# rz568m-power-data-v2.net
KiCad netlist of a schematic drawn in EAGLE
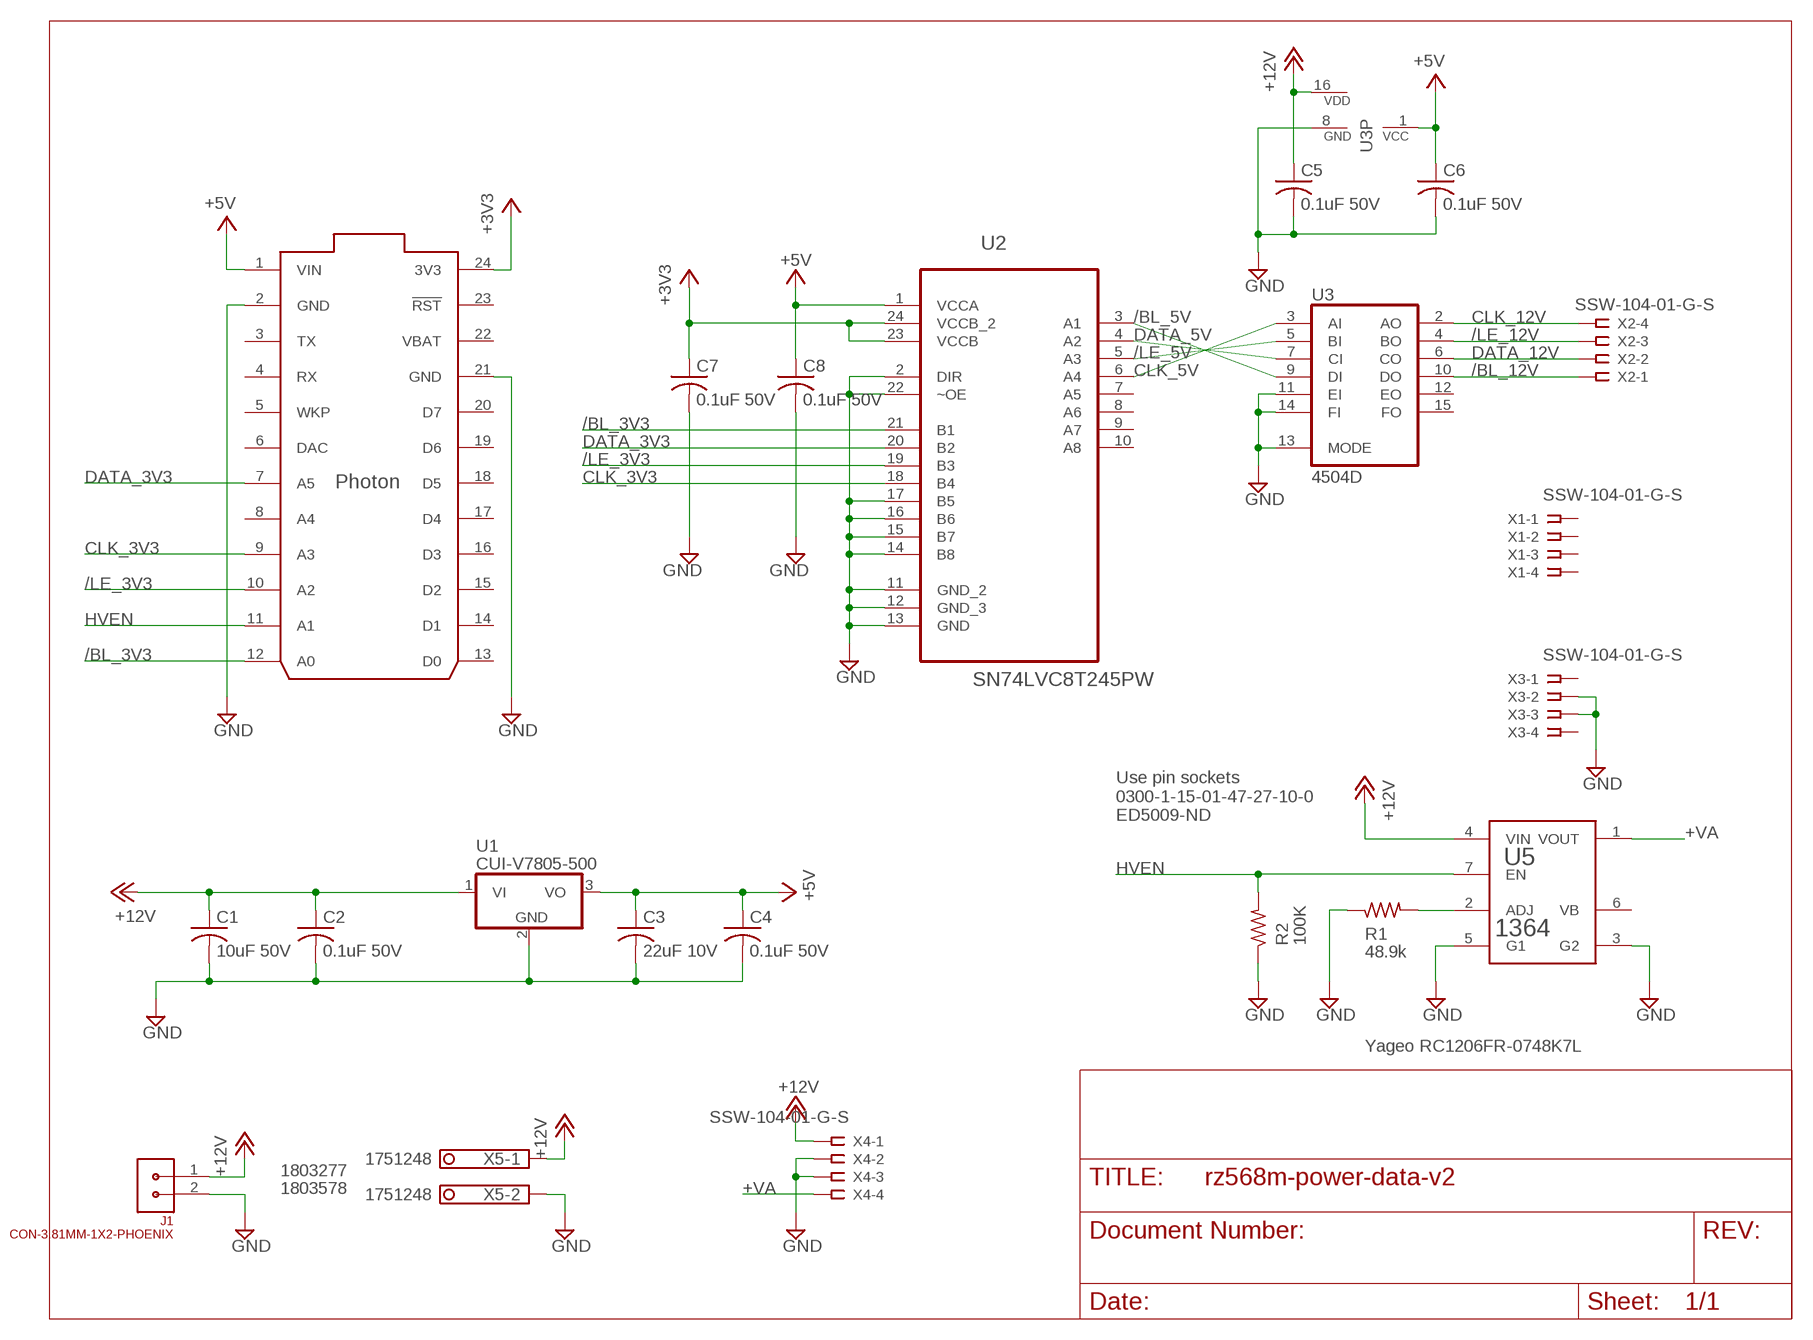
[diagram p0: schematic, sheet 1]

(export (version "E")
  (design (tool "Eeschema 10.0.6"))
  (components
    (comp (ref "C1")
      (value "10uF 50V")
      (footprint "eagle-import:C1210K")
      (fields (field (name "MFR") "KEMET") (field (name "MFR_PART_NO") "C1210C106K5RACTU"))
      (libsource (lib "eagle-import") (part "C-USC1210K"))
    )
    (comp (ref "C2")
      (value "0.1uF 50V")
      (footprint "eagle-import:C1206K")
      (fields (field (name "MFR") "KEMET") (field (name "MFR_PART_NO") "C1206S104M5RACTU"))
      (libsource (lib "eagle-import") (part "C-USC1206K"))
    )
    (comp (ref "C3")
      (value "22uF 10V")
      (footprint "eagle-import:C1206K")
      (fields (field (name "MFR") "KEMET") (field (name "MFR_PART_NO") "C1206C226K8RAC7800"))
      (libsource (lib "eagle-import") (part "C-USC1206K"))
    )
    (comp (ref "C4")
      (value "0.1uF 50V")
      (footprint "eagle-import:C1206K")
      (fields (field (name "MFR") "KEMET") (field (name "MFR_PART_NO") "C1206S104M5RACTU"))
      (libsource (lib "eagle-import") (part "C-USC1206K"))
    )
    (comp (ref "C5")
      (value "0.1uF 50V")
      (footprint "eagle-import:C0805K")
      (fields (field (name "MFR") "KEMET") (field (name "MFR_PART_NO") "C1206S104M5RACTU"))
      (libsource (lib "eagle-import") (part "C-USC0805K"))
    )
    (comp (ref "C6")
      (value "0.1uF 50V")
      (footprint "eagle-import:C0805K")
      (fields (field (name "MFR") "KEMET") (field (name "MFR_PART_NO") "C1206S104M5RACTU"))
      (libsource (lib "eagle-import") (part "C-USC0805K"))
    )
    (comp (ref "C7")
      (value "0.1uF 50V")
      (footprint "eagle-import:C0805K")
      (fields (field (name "MFR") "KEMET") (field (name "MFR_PART_NO") "C1206S104M5RACTU"))
      (libsource (lib "eagle-import") (part "C-USC0805K"))
    )
    (comp (ref "C8")
      (value "0.1uF 50V")
      (footprint "eagle-import:C0805K")
      (fields (field (name "MFR") "KEMET") (field (name "MFR_PART_NO") "C1206S104M5RACTU"))
      (libsource (lib "eagle-import") (part "C-USC0805K"))
    )
    (comp (ref "J1")
      (value "CON-3.81MM-1X2-PHOENIX")
      (footprint "eagle-import:CON-PHOENIX-3.81-1X2-RA")
      (libsource (lib "eagle-import") (part "CON-3.81MM-1X2-PHOENIX"))
    )
    (comp (ref "R1")
      (value "48.9k")
      (footprint "eagle-import:R1206")
      (libsource (lib "eagle-import") (part "R-US_R1206"))
    )
    (comp (ref "R2")
      (value "100K")
      (footprint "eagle-import:R1206")
      (libsource (lib "eagle-import") (part "R-US_R1206"))
    )
    (comp (ref "U1")
      (value "CUI-V7805-500")
      (footprint "eagle-import:CUI-78XX-500")
      (libsource (lib "eagle-import") (part "CUI-V7803-500"))
    )
    (comp (ref "U2")
      (value "SN74LVC8T245PW")
      (footprint "eagle-import:SOP65P640X120-24N")
      (fields (field (name "MPN") "SN74AVC8T245PW"))
      (libsource (lib "eagle-import") (part "SN74AVC8T245PW"))
    )
    (comp (ref "U3")
      (value "4504D")
      (footprint "eagle-import:SO16")
      (libsource (lib "eagle-import") (part "4504D"))
    )
    (comp (ref "U4")
      (value "PHOTON_WITH_HEADERS")
      (footprint "eagle-import:PHOTON")
      (libsource (lib "eagle-import") (part "PHOTON_WITH_HEADERS"))
    )
    (comp (ref "U5")
      (value "1364")
      (footprint "eagle-import:1364")
      (libsource (lib "eagle-import") (part "1364"))
    )
    (comp (ref "X1")
      (value "SSW-104-01-G-S")
      (footprint "eagle-import:SSW-104-02-S-S")
      (fields (field (name "MPN") "SSW-104-02-S-S"))
      (libsource (lib "eagle-import") (part "SSW-104-02-S-S"))
    )
    (comp (ref "X2")
      (value "SSW-104-01-G-S")
      (footprint "eagle-import:SSW-104-02-S-S")
      (fields (field (name "MPN") "SSW-104-02-S-S"))
      (libsource (lib "eagle-import") (part "SSW-104-02-S-S"))
    )
    (comp (ref "X3")
      (value "SSW-104-01-G-S")
      (footprint "eagle-import:SSW-104-02-S-S")
      (fields (field (name "MPN") "SSW-104-02-S-S"))
      (libsource (lib "eagle-import") (part "SSW-104-02-S-S"))
    )
    (comp (ref "X4")
      (value "SSW-104-01-G-S")
      (footprint "eagle-import:SSW-104-02-S-S")
      (fields (field (name "MPN") "SSW-104-02-S-S"))
      (libsource (lib "eagle-import") (part "SSW-104-02-S-S"))
    )
    (comp (ref "X5")
      (value "1751248")
      (footprint "eagle-import:1751248")
      (libsource (lib "eagle-import") (part "1751248"))
    )
  )
  (nets
    (net (code "1") (name "+3V3") (class "Default")
      (node (ref "C7") (pin "1") (pinfunction "1_1") (pintype "passive"))
      (node (ref "U2") (pin "23") (pinfunction "VCCB_23") (pintype "power_in"))
      (node (ref "U2") (pin "24") (pinfunction "VCCB_2_24") (pintype "power_in"))
      (node (ref "U4") (pin "24") (pinfunction "3V3_24") (pintype "power_in"))
    )
    (net (code "2") (name "+5V") (class "Default")
      (node (ref "C3") (pin "1") (pinfunction "1_1") (pintype "passive"))
      (node (ref "C4") (pin "1") (pinfunction "1_1") (pintype "passive"))
      (node (ref "C6") (pin "1") (pinfunction "1_1") (pintype "passive"))
      (node (ref "C8") (pin "1") (pinfunction "1_1") (pintype "passive"))
      (node (ref "U1") (pin "3") (pinfunction "VO_3") (pintype "passive"))
      (node (ref "U2") (pin "1") (pinfunction "VCCA_1") (pintype "power_in"))
      (node (ref "U3") (pin "1") (pinfunction "VCC_1") (pintype "power_in"))
      (node (ref "U4") (pin "1") (pinfunction "VIN_1") (pintype "power_in"))
    )
    (net (code "3") (name "+12V") (class "Default")
      (node (ref "C1") (pin "1") (pinfunction "1_1") (pintype "passive"))
      (node (ref "C2") (pin "1") (pinfunction "1_1") (pintype "passive"))
      (node (ref "C5") (pin "1") (pinfunction "1_1") (pintype "passive"))
      (node (ref "J1") (pin "1") (pinfunction "1_1") (pintype "bidirectional"))
      (node (ref "U1") (pin "1") (pinfunction "VI_1") (pintype "input"))
      (node (ref "U3") (pin "16") (pinfunction "VDD_16") (pintype "power_in"))
      (node (ref "U5") (pin "4") (pinfunction "VIN_4") (pintype "passive"))
      (node (ref "X4") (pin "1") (pinfunction "1_1") (pintype "passive"))
      (node (ref "X5") (pin "1") (pinfunction "K_1") (pintype "passive"))
    )
    (net (code "4") (name "/+VA") (class "Default")
      (node (ref "U5") (pin "1") (pinfunction "VOUT_1") (pintype "passive"))
      (node (ref "X4") (pin "4") (pinfunction "1_4") (pintype "passive"))
    )
    (net (code "5") (name "/CLK_3V3") (class "Default")
      (node (ref "U2") (pin "18") (pinfunction "B4_18") (pintype "bidirectional"))
      (node (ref "U4") (pin "9") (pinfunction "A3_9") (pintype "bidirectional"))
    )
    (net (code "6") (name "/CLK_5V") (class "Default")
      (node (ref "U2") (pin "6") (pinfunction "A4_6") (pintype "bidirectional"))
      (node (ref "U3") (pin "3") (pinfunction "AI_3") (pintype "input"))
    )
    (net (code "7") (name "/CLK_12V") (class "Default")
      (node (ref "U3") (pin "2") (pinfunction "AO_2") (pintype "output"))
      (node (ref "X2") (pin "4") (pinfunction "1_4") (pintype "passive"))
    )
    (net (code "8") (name "/DATA_3V3") (class "Default")
      (node (ref "U2") (pin "20") (pinfunction "B2_20") (pintype "bidirectional"))
      (node (ref "U4") (pin "7") (pinfunction "A5_7") (pintype "bidirectional"))
    )
    (net (code "9") (name "/DATA_5V") (class "Default")
      (node (ref "U2") (pin "4") (pinfunction "A2_4") (pintype "bidirectional"))
      (node (ref "U3") (pin "7") (pinfunction "CI_7") (pintype "input"))
    )
    (net (code "10") (name "/DATA_12V") (class "Default")
      (node (ref "U3") (pin "6") (pinfunction "CO_6") (pintype "output"))
      (node (ref "X2") (pin "2") (pinfunction "1_2") (pintype "passive"))
    )
    (net (code "11") (name "/HVEN") (class "Default")
      (node (ref "R2") (pin "2") (pinfunction "2_2") (pintype "passive"))
      (node (ref "U4") (pin "11") (pinfunction "A1_11") (pintype "bidirectional"))
      (node (ref "U5") (pin "7") (pinfunction "EN_7") (pintype "passive"))
    )
    (net (code "12") (name "/VBAT") (class "Default")
      (node (ref "U4") (pin "22") (pinfunction "VBAT_22") (pintype "power_in"))
    )
    (net (code "13") (name "/{slash}BL_3V3") (class "Default")
      (node (ref "U2") (pin "21") (pinfunction "B1_21") (pintype "bidirectional"))
      (node (ref "U4") (pin "12") (pinfunction "A0_12") (pintype "bidirectional"))
    )
    (net (code "14") (name "/{slash}BL_5V") (class "Default")
      (node (ref "U2") (pin "3") (pinfunction "A1_3") (pintype "bidirectional"))
      (node (ref "U3") (pin "9") (pinfunction "DI_9") (pintype "input"))
    )
    (net (code "15") (name "/{slash}BL_12V") (class "Default")
      (node (ref "U3") (pin "10") (pinfunction "DO_10") (pintype "output"))
      (node (ref "X2") (pin "1") (pinfunction "1_1") (pintype "passive"))
    )
    (net (code "16") (name "/{slash}LE_3V3") (class "Default")
      (node (ref "U2") (pin "19") (pinfunction "B3_19") (pintype "bidirectional"))
      (node (ref "U4") (pin "10") (pinfunction "A2_10") (pintype "bidirectional"))
    )
    (net (code "17") (name "/{slash}LE_5V") (class "Default")
      (node (ref "U2") (pin "5") (pinfunction "A3_5") (pintype "bidirectional"))
      (node (ref "U3") (pin "5") (pinfunction "BI_5") (pintype "input"))
    )
    (net (code "18") (name "/{slash}LE_12V") (class "Default")
      (node (ref "U3") (pin "4") (pinfunction "BO_4") (pintype "output"))
      (node (ref "X2") (pin "3") (pinfunction "1_3") (pintype "passive"))
    )
    (net (code "19") (name "GND") (class "Default")
      (node (ref "C1") (pin "2") (pinfunction "2_2") (pintype "passive"))
      (node (ref "C2") (pin "2") (pinfunction "2_2") (pintype "passive"))
      (node (ref "C3") (pin "2") (pinfunction "2_2") (pintype "passive"))
      (node (ref "C4") (pin "2") (pinfunction "2_2") (pintype "passive"))
      (node (ref "C5") (pin "2") (pinfunction "2_2") (pintype "passive"))
      (node (ref "C6") (pin "2") (pinfunction "2_2") (pintype "passive"))
      (node (ref "C7") (pin "2") (pinfunction "2_2") (pintype "passive"))
      (node (ref "C8") (pin "2") (pinfunction "2_2") (pintype "passive"))
      (node (ref "J1") (pin "2") (pinfunction "2_2") (pintype "bidirectional"))
      (node (ref "R1") (pin "1") (pinfunction "1_1") (pintype "passive"))
      (node (ref "R2") (pin "1") (pinfunction "1_1") (pintype "passive"))
      (node (ref "U1") (pin "2") (pinfunction "GND_2") (pintype "passive"))
      (node (ref "U2") (pin "11") (pinfunction "GND_2_11") (pintype "passive"))
      (node (ref "U2") (pin "12") (pinfunction "GND_3_12") (pintype "passive"))
      (node (ref "U2") (pin "13") (pinfunction "GND_13") (pintype "passive"))
      (node (ref "U2") (pin "14") (pinfunction "B8_14") (pintype "bidirectional"))
      (node (ref "U2") (pin "15") (pinfunction "B7_15") (pintype "bidirectional"))
      (node (ref "U2") (pin "16") (pinfunction "B6_16") (pintype "bidirectional"))
      (node (ref "U2") (pin "17") (pinfunction "B5_17") (pintype "bidirectional"))
      (node (ref "U2") (pin "2") (pinfunction "DIR_2") (pintype "input"))
      (node (ref "U2") (pin "22") (pinfunction "~{OE}_22") (pintype "input"))
      (node (ref "U3") (pin "11") (pinfunction "EI_11") (pintype "input"))
      (node (ref "U3") (pin "13") (pinfunction "MODE_13") (pintype "input"))
      (node (ref "U3") (pin "14") (pinfunction "FI_14") (pintype "input"))
      (node (ref "U3") (pin "8") (pinfunction "GND_8") (pintype "power_in"))
      (node (ref "U4") (pin "2") (pinfunction "GND_2") (pintype "power_in"))
      (node (ref "U4") (pin "21") (pinfunction "GND_21") (pintype "power_in"))
      (node (ref "U5") (pin "3") (pinfunction "G2_3") (pintype "passive"))
      (node (ref "U5") (pin "5") (pinfunction "G1_5") (pintype "passive"))
      (node (ref "X3") (pin "2") (pinfunction "1_2") (pintype "passive"))
      (node (ref "X3") (pin "3") (pinfunction "1_3") (pintype "passive"))
      (node (ref "X4") (pin "2") (pinfunction "1_2") (pintype "passive"))
      (node (ref "X4") (pin "3") (pinfunction "1_3") (pintype "passive"))
      (node (ref "X5") (pin "2") (pinfunction "K_2") (pintype "passive"))
    )
    (net (code "20") (name "Net-(U5-ADJ)") (class "Default")
      (node (ref "R1") (pin "2") (pinfunction "2_2") (pintype "passive"))
      (node (ref "U5") (pin "2") (pinfunction "ADJ_2") (pintype "passive"))
    )
    (net (code "21") (name "unconnected-(U2-A5-Pad7)") (class "Default")
      (node (ref "U2") (pin "7") (pinfunction "A5_7") (pintype "bidirectional"))
    )
    (net (code "22") (name "unconnected-(U2-A6-Pad8)") (class "Default")
      (node (ref "U2") (pin "8") (pinfunction "A6_8") (pintype "bidirectional"))
    )
    (net (code "23") (name "unconnected-(U2-A7-Pad9)") (class "Default")
      (node (ref "U2") (pin "9") (pinfunction "A7_9") (pintype "bidirectional"))
    )
    (net (code "24") (name "unconnected-(U2-A8-Pad10)") (class "Default")
      (node (ref "U2") (pin "10") (pinfunction "A8_10") (pintype "bidirectional"))
    )
    (net (code "25") (name "unconnected-(U3A-EO-Pad12)") (class "Default")
      (node (ref "U3") (pin "12") (pinfunction "EO_12") (pintype "output"))
    )
    (net (code "26") (name "unconnected-(U3A-FO-Pad15)") (class "Default")
      (node (ref "U3") (pin "15") (pinfunction "FO_15") (pintype "output"))
    )
    (net (code "27") (name "unconnected-(U4-A4-Pad8)") (class "Default")
      (node (ref "U4") (pin "8") (pinfunction "A4_8") (pintype "bidirectional"))
    )
    (net (code "28") (name "unconnected-(U4-D0-Pad13)") (class "Default")
      (node (ref "U4") (pin "13") (pinfunction "D0_13") (pintype "bidirectional"))
    )
    (net (code "29") (name "unconnected-(U4-D1-Pad14)") (class "Default")
      (node (ref "U4") (pin "14") (pinfunction "D1_14") (pintype "bidirectional"))
    )
    (net (code "30") (name "unconnected-(U4-D2-Pad15)") (class "Default")
      (node (ref "U4") (pin "15") (pinfunction "D2_15") (pintype "bidirectional"))
    )
    (net (code "31") (name "unconnected-(U4-D3-Pad16)") (class "Default")
      (node (ref "U4") (pin "16") (pinfunction "D3_16") (pintype "bidirectional"))
    )
    (net (code "32") (name "unconnected-(U4-D4-Pad17)") (class "Default")
      (node (ref "U4") (pin "17") (pinfunction "D4_17") (pintype "bidirectional"))
    )
    (net (code "33") (name "unconnected-(U4-D5-Pad18)") (class "Default")
      (node (ref "U4") (pin "18") (pinfunction "D5_18") (pintype "bidirectional"))
    )
    (net (code "34") (name "unconnected-(U4-D6-Pad19)") (class "Default")
      (node (ref "U4") (pin "19") (pinfunction "D6_19") (pintype "bidirectional"))
    )
    (net (code "35") (name "unconnected-(U4-D7-Pad20)") (class "Default")
      (node (ref "U4") (pin "20") (pinfunction "D7_20") (pintype "bidirectional"))
    )
    (net (code "36") (name "unconnected-(U4-DAC-Pad6)") (class "Default")
      (node (ref "U4") (pin "6") (pinfunction "DAC_6") (pintype "bidirectional"))
    )
    (net (code "37") (name "unconnected-(U4-RX-Pad4)") (class "Default")
      (node (ref "U4") (pin "4") (pinfunction "RX_4") (pintype "bidirectional"))
    )
    (net (code "38") (name "unconnected-(U4-TX-Pad3)") (class "Default")
      (node (ref "U4") (pin "3") (pinfunction "TX_3") (pintype "bidirectional"))
    )
    (net (code "39") (name "unconnected-(U4-WKP-Pad5)") (class "Default")
      (node (ref "U4") (pin "5") (pinfunction "WKP_5") (pintype "bidirectional"))
    )
    (net (code "40") (name "unconnected-(U4-~{RST}-Pad23)") (class "Default")
      (node (ref "U4") (pin "23") (pinfunction "~{RST}_23") (pintype "bidirectional"))
    )
    (net (code "41") (name "unconnected-(U5-VB-Pad6)") (class "Default")
      (node (ref "U5") (pin "6") (pinfunction "VB_6") (pintype "passive"))
    )
    (net (code "42") (name "unconnected-(X1-Pad1)") (class "Default")
      (node (ref "X1") (pin "1") (pinfunction "1_1") (pintype "passive"))
    )
    (net (code "43") (name "unconnected-(X1B-1-Pad2)") (class "Default")
      (node (ref "X1") (pin "2") (pinfunction "1_2") (pintype "passive"))
    )
    (net (code "44") (name "unconnected-(X1C-1-Pad3)") (class "Default")
      (node (ref "X1") (pin "3") (pinfunction "1_3") (pintype "passive"))
    )
    (net (code "45") (name "unconnected-(X1D-1-Pad4)") (class "Default")
      (node (ref "X1") (pin "4") (pinfunction "1_4") (pintype "passive"))
    )
    (net (code "46") (name "unconnected-(X3-Pad1)") (class "Default")
      (node (ref "X3") (pin "1") (pinfunction "1_1") (pintype "passive"))
    )
    (net (code "47") (name "unconnected-(X3D-1-Pad4)") (class "Default")
      (node (ref "X3") (pin "4") (pinfunction "1_4") (pintype "passive"))
    )
  )
)
